# power.net
KiCad netlist of a schematic drawn in Altium Designer
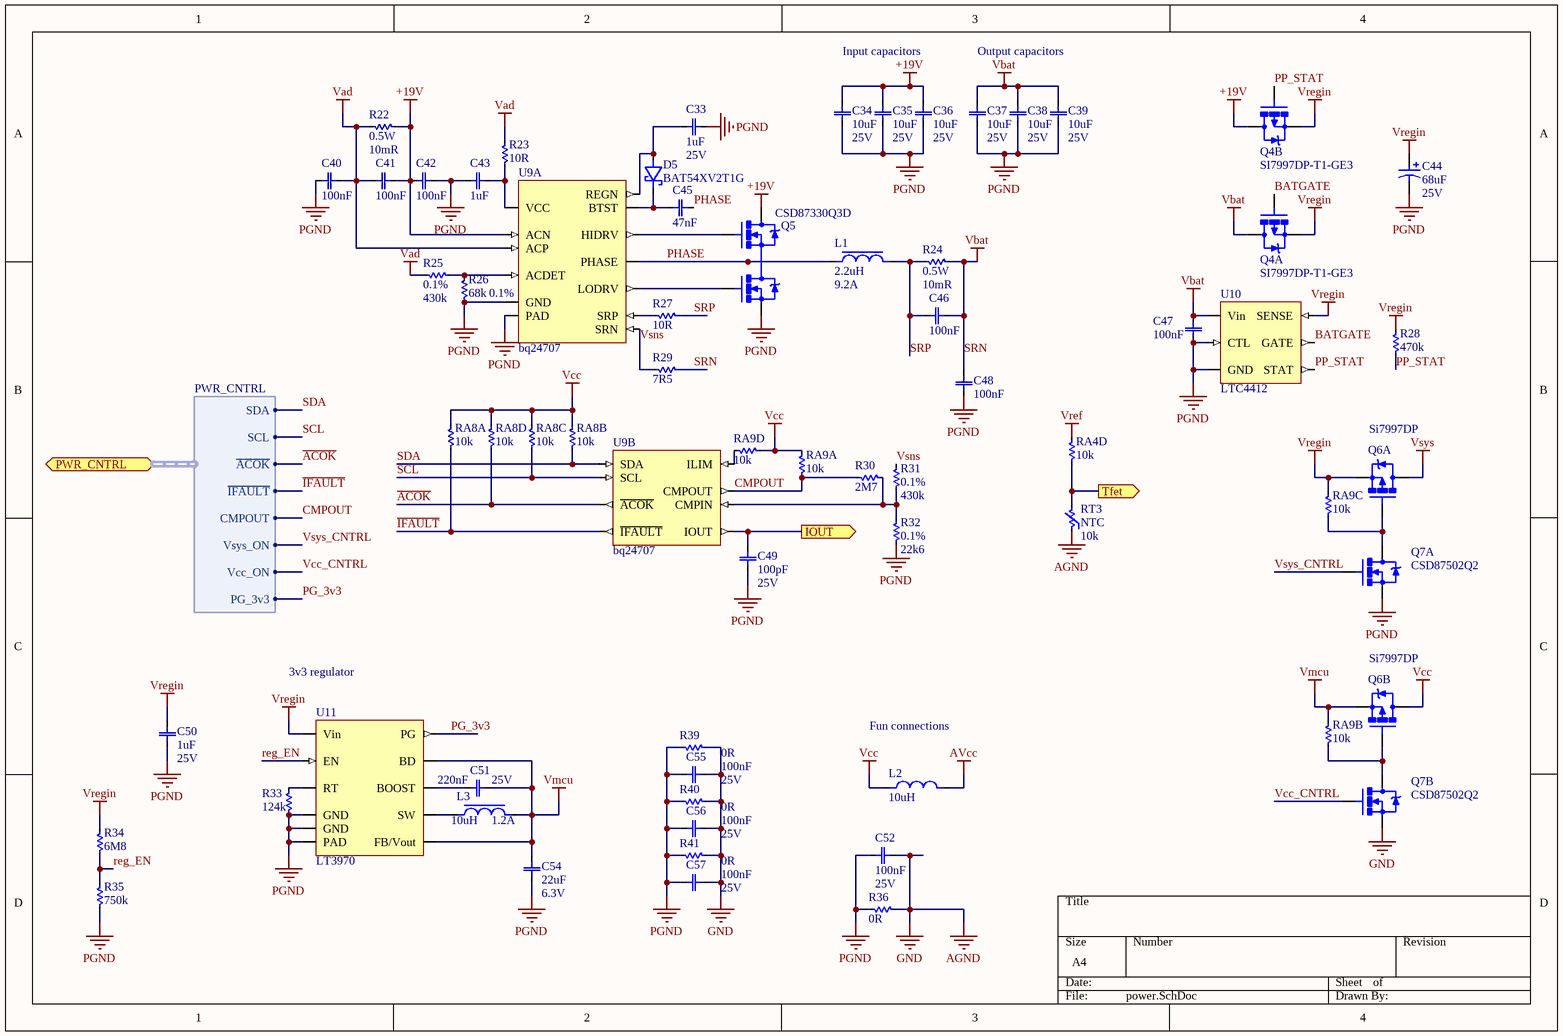
[diagram p0: power.SchDoc]

(export (version "E")
  (design (tool "Eeschema 10.0.6"))
  (components
    (comp (ref "C33")
      (value "25V")
      (footprint "CAP0603")
      (fields
        (field (name "TOLERANCE") "10%")
        (field (name "CAPACITANCE") "1uF")
        (field (name "VOLTAGE") "25V")
      )
      (libsource (lib "passive") (part "capacitor"))
    )
    (comp (ref "C34")
      (value "~")
      (footprint "CAP1206")
      (fields
        (field (name "TOLERANCE") "10%")
        (field (name "CAPACITANCE") "10uF")
        (field (name "VOLTAGE") "25V")
      )
      (libsource (lib "passive") (part "capacitor"))
    )
    (comp (ref "C35")
      (value "~")
      (footprint "CAP1206")
      (fields
        (field (name "TOLERANCE") "10%")
        (field (name "CAPACITANCE") "10uF")
        (field (name "VOLTAGE") "25V")
      )
      (libsource (lib "passive") (part "capacitor"))
    )
    (comp (ref "C36")
      (value "~")
      (footprint "CAP1206")
      (fields
        (field (name "TOLERANCE") "10%")
        (field (name "CAPACITANCE") "10uF")
        (field (name "VOLTAGE") "25V")
      )
      (libsource (lib "passive") (part "capacitor"))
    )
    (comp (ref "C37")
      (value "~")
      (footprint "CAP1206")
      (fields
        (field (name "TOLERANCE") "10%")
        (field (name "CAPACITANCE") "10uF")
        (field (name "VOLTAGE") "25V")
      )
      (libsource (lib "passive") (part "capacitor"))
    )
    (comp (ref "C38")
      (value "~")
      (footprint "CAP1206")
      (fields
        (field (name "TOLERANCE") "10%")
        (field (name "CAPACITANCE") "10uF")
        (field (name "VOLTAGE") "25V")
      )
      (libsource (lib "passive") (part "capacitor"))
    )
    (comp (ref "C39")
      (value "~")
      (footprint "CAP1206")
      (fields
        (field (name "TOLERANCE") "10%")
        (field (name "CAPACITANCE") "10uF")
        (field (name "VOLTAGE") "25V")
      )
      (libsource (lib "passive") (part "capacitor"))
    )
    (comp (ref "C40")
      (value "0nF")
      (footprint "CAP0402")
      (fields (field (name "CAPACITANCE") "100nF") (field (name "TOLERANCE") "10%"))
      (libsource (lib "passive") (part "capacitor"))
    )
    (comp (ref "C41")
      (value "0nF")
      (footprint "CAP0402")
      (fields (field (name "CAPACITANCE") "100nF") (field (name "TOLERANCE") "10%"))
      (libsource (lib "passive") (part "capacitor"))
    )
    (comp (ref "C42")
      (value "0nF")
      (footprint "CAP0402")
      (fields (field (name "CAPACITANCE") "100nF") (field (name "TOLERANCE") "10%"))
      (libsource (lib "passive") (part "capacitor"))
    )
    (comp (ref "C43") (value "1uF") (footprint "CAP0603") (libsource (lib "passive") (part "capacitor")))
    (comp (ref "C44")
      (value "cap_pol")
      (footprint "CAPAE6253X61L")
      (fields
        (field (name "TOLERANCE") "20%")
        (field (name "CAPACITANCE") "68uF")
        (field (name "VOLTAGE") "25V")
      )
      (libsource (lib "passive") (part "cap_pol"))
    )
    (comp (ref "C45")
      (value "~")
      (footprint "CAP0402")
      (fields (field (name "TOLERANCE") "10%") (field (name "CAPACITANCE") "47nF"))
      (libsource (lib "passive") (part "capacitor"))
    )
    (comp (ref "C46")
      (value "0nF")
      (footprint "CAP0402")
      (fields (field (name "CAPACITANCE") "100nF") (field (name "TOLERANCE") "10%"))
      (libsource (lib "passive") (part "capacitor"))
    )
    (comp (ref "C47")
      (value "0nF")
      (footprint "CAP0402")
      (fields (field (name "CAPACITANCE") "100nF") (field (name "TOLERANCE") "10%"))
      (libsource (lib "passive") (part "capacitor"))
    )
    (comp (ref "C48")
      (value "0nF")
      (footprint "CAP0402")
      (fields (field (name "CAPACITANCE") "100nF") (field (name "TOLERANCE") "10%"))
      (libsource (lib "passive") (part "capacitor"))
    )
    (comp (ref "C49")
      (value "25V")
      (footprint "CAP0402")
      (fields
        (field (name "TOLERANCE") "10%")
        (field (name "CAPACITANCE") "100pF")
        (field (name "VOLTAGE") "25V")
      )
      (libsource (lib "passive") (part "capacitor"))
    )
    (comp (ref "C50")
      (value "25V")
      (footprint "CAP0603")
      (fields
        (field (name "TOLERANCE") "10%")
        (field (name "CAPACITANCE") "1uF")
        (field (name "VOLTAGE") "25V")
      )
      (libsource (lib "passive") (part "capacitor"))
    )
    (comp (ref "C51")
      (value "25V")
      (footprint "CAP0402")
      (fields
        (field (name "TOLERANCE") "10%")
        (field (name "CAPACITANCE") "220nF")
        (field (name "VOLTAGE") "25V")
      )
      (libsource (lib "passive") (part "capacitor"))
    )
    (comp (ref "C52")
      (value "25V")
      (footprint "CAP0402")
      (fields
        (field (name "TOLERANCE") "10%")
        (field (name "CAPACITANCE") "100nF")
        (field (name "VOLTAGE") "25V")
      )
      (libsource (lib "passive") (part "capacitor"))
    )
    (comp (ref "C54")
      (value "~")
      (footprint "CAP0805")
      (fields
        (field (name "TOLERANCE") "20%")
        (field (name "CAPACITANCE") "22uF")
        (field (name "VOLTAGE") "6.3V")
      )
      (libsource (lib "passive") (part "capacitor"))
    )
    (comp (ref "C55")
      (value "25V")
      (footprint "CAP0402")
      (fields
        (field (name "TOLERANCE") "10%")
        (field (name "CAPACITANCE") "100nF")
        (field (name "VOLTAGE") "25V")
      )
      (libsource (lib "passive") (part "capacitor"))
    )
    (comp (ref "C56")
      (value "25V")
      (footprint "CAP0402")
      (fields
        (field (name "TOLERANCE") "10%")
        (field (name "CAPACITANCE") "100nF")
        (field (name "VOLTAGE") "25V")
      )
      (libsource (lib "passive") (part "capacitor"))
    )
    (comp (ref "C57")
      (value "25V")
      (footprint "CAP0402")
      (fields
        (field (name "TOLERANCE") "10%")
        (field (name "CAPACITANCE") "100nF")
        (field (name "VOLTAGE") "25V")
      )
      (libsource (lib "passive") (part "capacitor"))
    )
    (comp (ref "D5")
      (value "BAT54XV2T1G")
      (footprint "SOD523")
      (libsource (lib "diodes") (part "Schottky diode"))
    )
    (comp (ref "L1")
      (value "XAL5030-222MEC")
      (footprint "XAL5030-222MEC")
      (fields
        (field (name "TOLERANCE") "20%")
        (field (name "INDUCTANCE") "2.2uH")
        (field (name "SATURATION CURRENT") "9.2A")
      )
      (libsource (lib "passive") (part "power_inductor"))
    )
    (comp (ref "L2")
      (value "chip_inductor")
      (footprint "INDC0603")
      (fields (field (name "TOLERANCE") "20%") (field (name "INDUCTANCE") "10uH"))
      (libsource (lib "passive") (part "chip_inductor"))
    )
    (comp (ref "L3")
      (value "LPS4018-333MR")
      (footprint "LPS4018")
      (fields
        (field (name "TOLERANCE") "20%")
        (field (name "INDUCTANCE") "10uH")
        (field (name "SATURATION CURRENT") "1.2A")
      )
      (libsource (lib "passive") (part "power_inductor"))
    )
    (comp (ref "Q4")
      (value "SI7997DP-T1-GE3")
      (footprint "PowerPAK SO-8 DUAL")
      (libsource (lib "") (part "DUAL-PFET_3"))
    )
    (comp (ref "Q5") (value "CSD87330Q3D") (footprint "TI_Q3D") (libsource (lib "mosfets") (part "BUCKFET")))
    (comp (ref "Q6")
      (value "Si7997DP")
      (footprint "PowerPAK SO-8 DUAL")
      (libsource (lib "") (part "DUAL-PFET_2"))
    )
    (comp (ref "Q7")
      (value "CSD87502Q2")
      (footprint "SON65P200X80_HS-7L_DUALFET")
      (libsource (lib "mosfets") (part "DUAL-NFET"))
    )
    (comp (ref "R22")
      (value "0R")
      (footprint "RES0805")
      (fields
        (field (name "POWER") "0.5W")
        (field (name "TOLERANCE") "1%")
        (field (name "RESISTANCE") "10mR")
      )
      (libsource (lib "passive") (part "resistor"))
    )
    (comp (ref "R23")
      (value "0R")
      (footprint "RES0603")
      (fields
        (field (name "POWER") "0.125W")
        (field (name "TOLERANCE") "5%")
        (field (name "RESISTANCE") "10R")
      )
      (libsource (lib "passive") (part "resistor"))
    )
    (comp (ref "R24")
      (value "0R")
      (footprint "RES0805")
      (fields
        (field (name "POWER") "0.5W")
        (field (name "TOLERANCE") "1%")
        (field (name "RESISTANCE") "10mR")
      )
      (libsource (lib "passive") (part "resistor"))
    )
    (comp (ref "R25")
      (value "resistor")
      (footprint "RES0402")
      (fields
        (field (name "POWER") "0.063W")
        (field (name "TOLERANCE") "0.1%")
        (field (name "RESISTANCE") "430k")
      )
      (libsource (lib "passive") (part "resistor"))
    )
    (comp (ref "R26")
      (value "0R")
      (footprint "RES0402")
      (fields
        (field (name "POWER") "0,63W")
        (field (name "TOLERANCE") "0.1%")
        (field (name "RESISTANCE") "68k")
      )
      (libsource (lib "passive") (part "resistor"))
    )
    (comp (ref "R27")
      (value "resistor")
      (footprint "RES0402")
      (fields
        (field (name "POWER") "0.063W")
        (field (name "TOLERANCE") "1%")
        (field (name "RESISTANCE") "10R")
      )
      (libsource (lib "passive") (part "resistor"))
    )
    (comp (ref "R28")
      (value "resistor")
      (footprint "RES0402")
      (fields
        (field (name "POWER") "0.063W")
        (field (name "TOLERANCE") "1%")
        (field (name "RESISTANCE") "470k")
      )
      (libsource (lib "passive") (part "resistor"))
    )
    (comp (ref "R29")
      (value "resistor")
      (footprint "RES0402")
      (fields
        (field (name "POWER") "0.063W")
        (field (name "TOLERANCE") "1%")
        (field (name "RESISTANCE") "7R5")
      )
      (libsource (lib "passive") (part "resistor"))
    )
    (comp (ref "R30")
      (value "resistor")
      (footprint "RES0402")
      (fields
        (field (name "POWER") "0.063W")
        (field (name "TOLERANCE") "1%")
        (field (name "RESISTANCE") "2M7")
      )
      (libsource (lib "passive") (part "resistor"))
    )
    (comp (ref "R31")
      (value "resistor")
      (footprint "RES0402")
      (fields
        (field (name "POWER") "0.063W")
        (field (name "TOLERANCE") "0.1%")
        (field (name "RESISTANCE") "430k")
      )
      (libsource (lib "passive") (part "resistor"))
    )
    (comp (ref "R32")
      (value "resistor")
      (footprint "RES0402")
      (fields
        (field (name "POWER") "0.063W")
        (field (name "TOLERANCE") "0.1%")
        (field (name "RESISTANCE") "22k6")
      )
      (libsource (lib "passive") (part "resistor"))
    )
    (comp (ref "R33")
      (value "resistor")
      (footprint "RES0402")
      (fields
        (field (name "POWER") "0.063W")
        (field (name "TOLERANCE") "1%")
        (field (name "RESISTANCE") "124k")
      )
      (libsource (lib "passive") (part "resistor"))
    )
    (comp (ref "R34")
      (value "resistor")
      (footprint "RES0402")
      (fields
        (field (name "POWER") "0.063W")
        (field (name "TOLERANCE") "1%")
        (field (name "RESISTANCE") "6M8")
      )
      (libsource (lib "passive") (part "resistor"))
    )
    (comp (ref "R35")
      (value "resistor")
      (footprint "RES0402")
      (fields
        (field (name "POWER") "0.063W")
        (field (name "TOLERANCE") "1%")
        (field (name "RESISTANCE") "750k")
      )
      (libsource (lib "passive") (part "resistor"))
    )
    (comp (ref "R36")
      (value "resistor")
      (footprint "RES0402")
      (fields
        (field (name "POWER") "0.063W")
        (field (name "TOLERANCE") "1%")
        (field (name "RESISTANCE") "0R")
      )
      (libsource (lib "passive") (part "resistor"))
    )
    (comp (ref "R39")
      (value "resistor")
      (footprint "RES0402")
      (fields
        (field (name "POWER") "0.063W")
        (field (name "TOLERANCE") "1%")
        (field (name "RESISTANCE") "0R")
      )
      (libsource (lib "passive") (part "resistor"))
    )
    (comp (ref "R40")
      (value "resistor")
      (footprint "RES0402")
      (fields
        (field (name "POWER") "0.063W")
        (field (name "TOLERANCE") "1%")
        (field (name "RESISTANCE") "0R")
      )
      (libsource (lib "passive") (part "resistor"))
    )
    (comp (ref "R41")
      (value "resistor")
      (footprint "RES0402")
      (fields
        (field (name "POWER") "0.063W")
        (field (name "TOLERANCE") "1%")
        (field (name "RESISTANCE") "0R")
      )
      (libsource (lib "passive") (part "resistor"))
    )
    (comp (ref "RA4")
      (value "quad_resistor")
      (footprint "CAC-50P200X100-8L")
      (fields (field (name "RESISTANCE") "10k"))
      (libsource (lib "passive") (part "quad_resistor"))
    )
    (comp (ref "RA8")
      (value "10k")
      (footprint "CAC-50P200X100-8L")
      (libsource (lib "passive") (part "quad_resistor"))
    )
    (comp (ref "RA9")
      (value "quad_resistor")
      (footprint "CAC-50P200X100-8L")
      (fields (field (name "RESISTANCE") "10k"))
      (libsource (lib "passive") (part "quad_resistor"))
    )
    (comp (ref "RT3")
      (value "thermistor")
      (footprint "RES0402")
      (fields
        (field (name "POWER") "60mW")
        (field (name "TOLERANCE") "1%")
        (field (name "TYPE") "NTC")
        (field (name "RESISTANCE") "10k")
      )
      (libsource (lib "passive") (part "thermistor"))
    )
    (comp (ref "U9")
      (value "bq24707")
      (footprint "QFN50P350X350X100_HS-21L")
      (libsource (lib "power") (part "bq24707"))
    )
    (comp (ref "U10")
      (value "LTC4412")
      (footprint "SOT95P280X100-6L")
      (description "Low Loss PowerPath™ Controller in ThinSOT")
      (libsource (lib "power") (part "LTC4412"))
    )
    (comp (ref "U11")
      (value "LT3970")
      (footprint "DFN50P200X300X85_HS-11L")
      (description "40V, 350mA Step-Down Regulator with 2.5µA Quiescent Current and Integrated Diodes")
      (libsource (lib "power") (part "LT3970"))
    )
  )
  (nets
    (net (code "2") (name "+19V") (class "Default")
      (node (ref "C34") (pin "2") (pinfunction "2_2") (pintype "passive"))
      (node (ref "C35") (pin "2") (pinfunction "2_2") (pintype "passive"))
      (node (ref "C36") (pin "2") (pinfunction "2_2") (pintype "passive"))
      (node (ref "C41") (pin "2") (pinfunction "2_2") (pintype "passive"))
      (node (ref "C42") (pin "1") (pinfunction "1_1") (pintype "passive"))
      (node (ref "Q4") (pin "D2") (pinfunction "D2_D2") (pintype "passive"))
      (node (ref "Q5") (pin "D1") (pinfunction "D1_D1") (pintype "passive"))
      (node (ref "R22") (pin "2") (pinfunction "2_2") (pintype "passive"))
      (node (ref "U9") (pin "1") (pinfunction "ACN_1") (pintype "input"))
    )
    (net (code "3") (name "/BATGATE") (class "Default")
      (node (ref "Q4") (pin "G1") (pinfunction "G1_G1") (pintype "passive"))
      (node (ref "U10") (pin "5") (pinfunction "GATE_5") (pintype "output"))
    )
    (net (code "4") (name "/CMPOUT") (class "Default")
      (node (ref "R30") (pin "1") (pinfunction "1_1") (pintype "passive"))
      (node (ref "RA9") (pin "8") (pinfunction "8_8") (pintype "passive"))
      (node (ref "U9") (pin "3") (pinfunction "CMPOUT_3") (pintype "output"))
    )
    (net (code "5") (name "/IOUT") (class "Default")
      (node (ref "C49") (pin "2") (pinfunction "2_2") (pintype "passive"))
      (node (ref "U9") (pin "7") (pinfunction "IOUT_7") (pintype "output"))
    )
    (net (code "6") (name "/PG_3v3") (class "Default")
      (node (ref "U11") (pin "9") (pinfunction "PG_9") (pintype "output"))
    )
    (net (code "7") (name "/PHASE") (class "Default")
      (node (ref "C45") (pin "2") (pinfunction "2_2") (pintype "passive"))
      (node (ref "L1") (pin "1") (pinfunction "1_1") (pintype "power_in"))
      (node (ref "Q5") (pin "D2") (pinfunction "D2_D2") (pintype "passive"))
      (node (ref "Q5") (pin "S1") (pinfunction "S1_S1") (pintype "passive"))
      (node (ref "U9") (pin "19") (pinfunction "PHASE_19") (pintype "passive"))
    )
    (net (code "8") (name "/PP_STAT") (class "Default")
      (node (ref "Q4") (pin "G2") (pinfunction "G2_G2") (pintype "passive"))
      (node (ref "R28") (pin "1") (pinfunction "1_1") (pintype "passive"))
      (node (ref "U10") (pin "6") (pinfunction "STAT_6") (pintype "output"))
    )
    (net (code "9") (name "/SCL") (class "Default")
      (node (ref "RA8") (pin "4") (pinfunction "4_4") (pintype "passive"))
      (node (ref "U9") (pin "9") (pinfunction "SCL_9") (pintype "input"))
    )
    (net (code "10") (name "/SDA") (class "Default")
      (node (ref "RA8") (pin "3") (pinfunction "3_3") (pintype "passive"))
      (node (ref "U9") (pin "8") (pinfunction "SDA_8") (pintype "input"))
    )
    (net (code "11") (name "/SRP") (class "Default")
      (node (ref "C46") (pin "1") (pinfunction "1_1") (pintype "passive"))
      (node (ref "L1") (pin "2") (pinfunction "2_2") (pintype "power_in"))
      (node (ref "R24") (pin "1") (pinfunction "1_1") (pintype "passive"))
      (node (ref "R27") (pin "2") (pinfunction "2_2") (pintype "passive"))
    )
    (net (code "12") (name "/Tfet") (class "Default")
      (node (ref "RA4") (pin "7") (pinfunction "7_7") (pintype "passive"))
      (node (ref "RT3") (pin "2") (pinfunction "2_2") (pintype "passive"))
    )
    (net (code "13") (name "/Vcc_CNTRL") (class "Default")
      (node (ref "Q7") (pin "G2") (pinfunction "G2_G2") (pintype "passive"))
    )
    (net (code "14") (name "/Vsns") (class "Default")
      (node (ref "R29") (pin "1") (pinfunction "1_1") (pintype "passive"))
      (node (ref "R31") (pin "1") (pinfunction "1_1") (pintype "passive"))
      (node (ref "U9") (pin "12") (pinfunction "SRN_12") (pintype "input"))
    )
    (net (code "15") (name "/Vsys_CNTRL") (class "Default")
      (node (ref "Q7") (pin "G1") (pinfunction "G1_G1") (pintype "passive"))
    )
    (net (code "16") (name "/reg_EN") (class "Default")
      (node (ref "R34") (pin "1") (pinfunction "1_1") (pintype "passive"))
      (node (ref "R35") (pin "2") (pinfunction "2_2") (pintype "passive"))
      (node (ref "U11") (pin "2") (pinfunction "EN_2") (pintype "input"))
    )
    (net (code "18") (name "/~{ACOK}") (class "Default")
      (node (ref "RA8") (pin "2") (pinfunction "2_2") (pintype "passive"))
      (node (ref "U9") (pin "5") (pinfunction "~{ACOK}_5") (pintype "output"))
    )
    (net (code "19") (name "/~{IFAULT}") (class "Default")
      (node (ref "RA8") (pin "1") (pinfunction "1_1") (pintype "passive"))
      (node (ref "U9") (pin "11") (pinfunction "~{IFAULT}_11") (pintype "output"))
    )
    (net (code "20") (name "AGND") (class "Default")
      (node (ref "C52") (pin "2") (pinfunction "2_2") (pintype "passive"))
      (node (ref "C55") (pin "2") (pinfunction "2_2") (pintype "passive"))
      (node (ref "C56") (pin "2") (pinfunction "2_2") (pintype "passive"))
      (node (ref "C57") (pin "2") (pinfunction "2_2") (pintype "passive"))
      (node (ref "Q7") (pin "S2") (pinfunction "S2_S2") (pintype "passive"))
      (node (ref "R36") (pin "1") (pinfunction "1_1") (pintype "passive"))
      (node (ref "R39") (pin "2") (pinfunction "2_2") (pintype "passive"))
      (node (ref "R40") (pin "2") (pinfunction "2_2") (pintype "passive"))
      (node (ref "R41") (pin "2") (pinfunction "2_2") (pintype "passive"))
      (node (ref "RT3") (pin "1") (pinfunction "1_1") (pintype "passive"))
    )
    (net (code "21") (name "AVcc") (class "Default")
      (node (ref "L2") (pin "2") (pinfunction "2_2") (pintype "power_in"))
    )
    (net (code "22") (name "Net-(D5-Anode)") (class "Default")
      (node (ref "C33") (pin "1") (pinfunction "1_1") (pintype "passive"))
      (node (ref "D5") (pin "A") (pinfunction "Anode_A") (pintype "power_in"))
      (node (ref "U9") (pin "16") (pinfunction "REGN_16") (pintype "output"))
    )
    (net (code "23") (name "Net-(D5-Cathode)") (class "Default")
      (node (ref "C45") (pin "1") (pinfunction "1_1") (pintype "passive"))
      (node (ref "D5") (pin "C") (pinfunction "Cathode_C") (pintype "power_in"))
      (node (ref "U9") (pin "17") (pinfunction "BTST_17") (pintype "power_in"))
    )
    (net (code "24") (name "Net-(Q6-PadG1)") (class "Default")
      (node (ref "Q6") (pin "G1") (pinfunction "G1_G1") (pintype "passive"))
      (node (ref "Q7") (pin "D1") (pinfunction "D1_D1") (pintype "passive"))
      (node (ref "RA9") (pin "5") (pinfunction "5_5") (pintype "passive"))
    )
    (net (code "25") (name "Net-(Q6-PadG2)") (class "Default")
      (node (ref "Q6") (pin "G2") (pinfunction "G2_G2") (pintype "passive"))
      (node (ref "Q7") (pin "D2") (pinfunction "D2_D2") (pintype "passive"))
      (node (ref "RA9") (pin "6") (pinfunction "6_6") (pintype "passive"))
    )
    (net (code "26") (name "Net-(U9A-ACDET)") (class "Default")
      (node (ref "R25") (pin "1") (pinfunction "1_1") (pintype "passive"))
      (node (ref "R26") (pin "2") (pinfunction "2_2") (pintype "passive"))
      (node (ref "U9") (pin "6") (pinfunction "ACDET_6") (pintype "input"))
    )
    (net (code "27") (name "Net-(U9A-HIDRV)") (class "Default")
      (node (ref "Q5") (pin "G1") (pinfunction "G1_G1") (pintype "passive"))
      (node (ref "U9") (pin "18") (pinfunction "HIDRV_18") (pintype "output"))
    )
    (net (code "28") (name "Net-(U9A-LODRV)") (class "Default")
      (node (ref "Q5") (pin "G2") (pinfunction "G2_G2") (pintype "passive"))
      (node (ref "U9") (pin "15") (pinfunction "LODRV_15") (pintype "output"))
    )
    (net (code "29") (name "Net-(U9A-SRP)") (class "Default")
      (node (ref "R27") (pin "1") (pinfunction "1_1") (pintype "passive"))
      (node (ref "U9") (pin "13") (pinfunction "SRP_13") (pintype "input"))
    )
    (net (code "30") (name "Net-(U9A-VCC)") (class "Default")
      (node (ref "C43") (pin "1") (pinfunction "1_1") (pintype "passive"))
      (node (ref "R23") (pin "2") (pinfunction "2_2") (pintype "passive"))
      (node (ref "U9") (pin "20") (pinfunction "VCC_20") (pintype "power_in"))
    )
    (net (code "31") (name "Net-(U9B-CMPIN)") (class "Default")
      (node (ref "R30") (pin "2") (pinfunction "2_2") (pintype "passive"))
      (node (ref "R31") (pin "2") (pinfunction "2_2") (pintype "passive"))
      (node (ref "R32") (pin "2") (pinfunction "2_2") (pintype "passive"))
      (node (ref "U9") (pin "4") (pinfunction "CMPIN_4") (pintype "input"))
    )
    (net (code "32") (name "Net-(U9B-ILIM)") (class "Default")
      (node (ref "RA9") (pin "7") (pinfunction "7_7") (pintype "passive"))
      (node (ref "U9") (pin "10") (pinfunction "ILIM_10") (pintype "input"))
    )
    (net (code "33") (name "Net-(U11-BOOST)") (class "Default")
      (node (ref "C51") (pin "1") (pinfunction "1_1") (pintype "passive"))
      (node (ref "U11") (pin "7") (pinfunction "BOOST_7") (pintype "power_in"))
    )
    (net (code "34") (name "Net-(U11-RT)") (class "Default")
      (node (ref "R33") (pin "1") (pinfunction "1_1") (pintype "passive"))
      (node (ref "U11") (pin "10") (pinfunction "RT_10") (pintype "passive"))
    )
    (net (code "35") (name "Net-(U11-SW)") (class "Default")
      (node (ref "L3") (pin "1") (pinfunction "1_1") (pintype "power_in"))
      (node (ref "U11") (pin "6") (pinfunction "SW_6") (pintype "power_in"))
    )
    (net (code "36") (name "PGND") (class "Default")
      (node (ref "C33") (pin "2") (pinfunction "2_2") (pintype "passive"))
      (node (ref "C34") (pin "1") (pinfunction "1_1") (pintype "passive"))
      (node (ref "C35") (pin "1") (pinfunction "1_1") (pintype "passive"))
      (node (ref "C36") (pin "1") (pinfunction "1_1") (pintype "passive"))
      (node (ref "C37") (pin "1") (pinfunction "1_1") (pintype "passive"))
      (node (ref "C38") (pin "1") (pinfunction "1_1") (pintype "passive"))
      (node (ref "C39") (pin "1") (pinfunction "1_1") (pintype "passive"))
      (node (ref "C40") (pin "1") (pinfunction "1_1") (pintype "passive"))
      (node (ref "C42") (pin "2") (pinfunction "2_2") (pintype "passive"))
      (node (ref "C43") (pin "2") (pinfunction "2_2") (pintype "passive"))
      (node (ref "C44") (pin "-") (pinfunction "-_-") (pintype "passive"))
      (node (ref "C47") (pin "1") (pinfunction "1_1") (pintype "passive"))
      (node (ref "C48") (pin "1") (pinfunction "1_1") (pintype "passive"))
      (node (ref "C49") (pin "1") (pinfunction "1_1") (pintype "passive"))
      (node (ref "C50") (pin "1") (pinfunction "1_1") (pintype "passive"))
      (node (ref "C52") (pin "1") (pinfunction "1_1") (pintype "passive"))
      (node (ref "C54") (pin "2") (pinfunction "2_2") (pintype "passive"))
      (node (ref "C55") (pin "1") (pinfunction "1_1") (pintype "passive"))
      (node (ref "C56") (pin "1") (pinfunction "1_1") (pintype "passive"))
      (node (ref "C57") (pin "1") (pinfunction "1_1") (pintype "passive"))
      (node (ref "Q5") (pin "S2") (pinfunction "S2_S2") (pintype "passive"))
      (node (ref "Q7") (pin "S1") (pinfunction "S1_S1") (pintype "passive"))
      (node (ref "R26") (pin "1") (pinfunction "1_1") (pintype "passive"))
      (node (ref "R32") (pin "1") (pinfunction "1_1") (pintype "passive"))
      (node (ref "R33") (pin "2") (pinfunction "2_2") (pintype "passive"))
      (node (ref "R35") (pin "1") (pinfunction "1_1") (pintype "passive"))
      (node (ref "R36") (pin "2") (pinfunction "2_2") (pintype "passive"))
      (node (ref "R39") (pin "1") (pinfunction "1_1") (pintype "passive"))
      (node (ref "R40") (pin "1") (pinfunction "1_1") (pintype "passive"))
      (node (ref "R41") (pin "1") (pinfunction "1_1") (pintype "passive"))
      (node (ref "U10") (pin "2") (pinfunction "GND_2") (pintype "power_in"))
      (node (ref "U10") (pin "3") (pinfunction "CTL_3") (pintype "input"))
      (node (ref "U11") (pin "11") (pinfunction "PAD_11") (pintype "power_in"))
      (node (ref "U11") (pin "4") (pinfunction "GND_4") (pintype "power_in"))
      (node (ref "U11") (pin "5") (pinfunction "GND_5") (pintype "power_in"))
      (node (ref "U9") (pin "14") (pinfunction "GND_14") (pintype "power_in"))
      (node (ref "U9") (pin "21") (pinfunction "PAD_21") (pintype "power_in"))
    )
    (net (code "37") (name "Vad") (class "Default")
      (node (ref "C40") (pin "2") (pinfunction "2_2") (pintype "passive"))
      (node (ref "C41") (pin "1") (pinfunction "1_1") (pintype "passive"))
      (node (ref "R22") (pin "1") (pinfunction "1_1") (pintype "passive"))
      (node (ref "R23") (pin "1") (pinfunction "1_1") (pintype "passive"))
      (node (ref "R25") (pin "2") (pinfunction "2_2") (pintype "passive"))
      (node (ref "U9") (pin "2") (pinfunction "ACP_2") (pintype "input"))
    )
    (net (code "38") (name "Vbat") (class "Default")
      (node (ref "C37") (pin "2") (pinfunction "2_2") (pintype "passive"))
      (node (ref "C38") (pin "2") (pinfunction "2_2") (pintype "passive"))
      (node (ref "C39") (pin "2") (pinfunction "2_2") (pintype "passive"))
      (node (ref "C46") (pin "2") (pinfunction "2_2") (pintype "passive"))
      (node (ref "C47") (pin "2") (pinfunction "2_2") (pintype "passive"))
      (node (ref "C48") (pin "2") (pinfunction "2_2") (pintype "passive"))
      (node (ref "Q4") (pin "D1") (pinfunction "D1_D1") (pintype "passive"))
      (node (ref "R24") (pin "2") (pinfunction "2_2") (pintype "passive"))
      (node (ref "R29") (pin "2") (pinfunction "2_2") (pintype "passive"))
      (node (ref "U10") (pin "1") (pinfunction "Vin_1") (pintype "power_in"))
    )
    (net (code "39") (name "Vcc") (class "Default")
      (node (ref "L2") (pin "1") (pinfunction "1_1") (pintype "power_in"))
      (node (ref "Q6") (pin "D2") (pinfunction "D2_D2") (pintype "passive"))
      (node (ref "RA8") (pin "5") (pinfunction "5_5") (pintype "passive"))
      (node (ref "RA8") (pin "6") (pinfunction "6_6") (pintype "passive"))
      (node (ref "RA8") (pin "7") (pinfunction "7_7") (pintype "passive"))
      (node (ref "RA8") (pin "8") (pinfunction "8_8") (pintype "passive"))
      (node (ref "RA9") (pin "1") (pinfunction "1_1") (pintype "passive"))
      (node (ref "RA9") (pin "2") (pinfunction "2_2") (pintype "passive"))
    )
    (net (code "40") (name "Vmcu") (class "Default")
      (node (ref "C51") (pin "2") (pinfunction "2_2") (pintype "passive"))
      (node (ref "C54") (pin "1") (pinfunction "1_1") (pintype "passive"))
      (node (ref "L3") (pin "2") (pinfunction "2_2") (pintype "power_in"))
      (node (ref "Q6") (pin "S2") (pinfunction "S2_S2") (pintype "passive"))
      (node (ref "RA9") (pin "3") (pinfunction "3_3") (pintype "passive"))
      (node (ref "U11") (pin "1") (pinfunction "FB/Vout_1") (pintype "power_in"))
      (node (ref "U11") (pin "8") (pinfunction "BD_8") (pintype "power_in"))
    )
    (net (code "41") (name "Vref") (class "Default")
      (node (ref "RA4") (pin "2") (pinfunction "2_2") (pintype "passive"))
    )
    (net (code "42") (name "Vregin") (class "Default")
      (node (ref "C44") (pin "+") (pinfunction "+_+") (pintype "passive"))
      (node (ref "C50") (pin "2") (pinfunction "2_2") (pintype "passive"))
      (node (ref "Q4") (pin "S1") (pinfunction "S1_S1") (pintype "passive"))
      (node (ref "Q4") (pin "S2") (pinfunction "S2_S2") (pintype "passive"))
      (node (ref "Q6") (pin "S1") (pinfunction "S1_S1") (pintype "passive"))
      (node (ref "R28") (pin "2") (pinfunction "2_2") (pintype "passive"))
      (node (ref "R34") (pin "2") (pinfunction "2_2") (pintype "passive"))
      (node (ref "RA9") (pin "4") (pinfunction "4_4") (pintype "passive"))
      (node (ref "U10") (pin "4") (pinfunction "SENSE_4") (pintype "input"))
      (node (ref "U11") (pin "3") (pinfunction "Vin_3") (pintype "power_in"))
    )
    (net (code "43") (name "Vsys") (class "Default")
      (node (ref "Q6") (pin "D1") (pinfunction "D1_D1") (pintype "passive"))
    )
  )
)
